# Modbus_RTU.net
KiCad netlist of a schematic drawn in Altium Designer
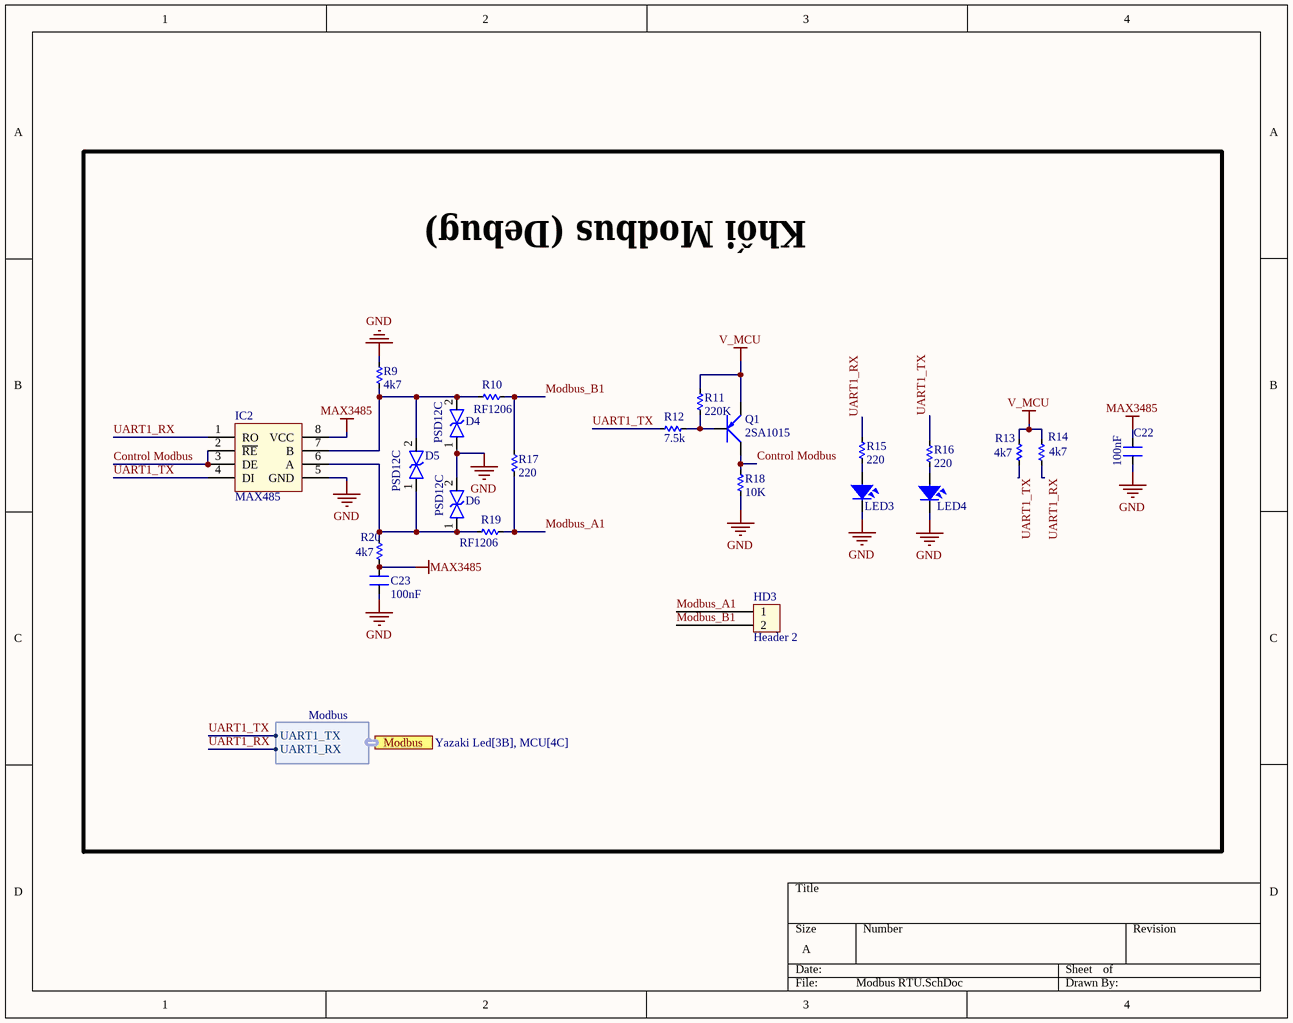
[diagram p0: Modbus RTU.SchDoc]

(export (version "E")
  (design (tool "Eeschema 10.0.6"))
  (components
    (comp (ref "C22") (value "100nF") (footprint "CN-SMD-0603") (libsource (lib "thu vien 3d") (part "CN")))
    (comp (ref "C23") (value "100nF") (footprint "CN-SMD-0603") (libsource (lib "thu vien 3d") (part "CN")))
    (comp (ref "D4")
      (value "PSD12C")
      (footprint "PSD12C")
      (description "diode tvs")
      (libsource (lib "Nichietsuvn") (part "PSD12C"))
    )
    (comp (ref "D5")
      (value "PSD12C")
      (footprint "PSD12C")
      (description "diode tvs")
      (libsource (lib "Nichietsuvn") (part "PSD12C"))
    )
    (comp (ref "D6")
      (value "PSD12C")
      (footprint "PSD12C")
      (description "diode tvs")
      (libsource (lib "Nichietsuvn") (part "PSD12C"))
    )
    (comp (ref "HD3") (value "Header 2") (footprint "Header_2") (libsource (lib "lpson") (part "Header2")))
    (comp (ref "IC2")
      (value "MAX485")
      (footprint "SO8")
      (description "RS232 - RS485 (Same sn75176)")
      (libsource (lib "thu vien 3d") (part "MAX485"))
    )
    (comp (ref "LED3")
      (value "LED")
      (footprint "LED-0805-Blue")
      (libsource (lib "thu vien 3d") (part "LED SMD"))
    )
    (comp (ref "LED4")
      (value "LED")
      (footprint "LED-0805-Blue")
      (libsource (lib "thu vien 3d") (part "LED SMD"))
    )
    (comp (ref "Q1")
      (value "2SA1015")
      (footprint "SOT23-321")
      (description "PNP 600mW, ECB")
      (libsource (lib "thu vien 3d") (part "2SA1015"))
    )
    (comp (ref "R9")
      (value "4k7")
      (footprint "RES-SMD-0603")
      (description "Resistor")
      (fields
        (field (name "MANUFACTURER") "Generic Components")
        (field (name "PUBLISHER") "Altium Hobart Technology Centre")
      )
      (libsource (lib "thu vien 3d") (part "Res-SMD"))
    )
    (comp (ref "R10")
      (value "RF1206")
      (footprint "RES-SMD-1206")
      (description "Resistor")
      (fields
        (field (name "MANUFACTURER") "Generic Components")
        (field (name "PUBLISHER") "Altium Hobart Technology Centre")
      )
      (libsource (lib "thu vien 3d") (part "Res-SMD"))
    )
    (comp (ref "R11")
      (value "220K")
      (footprint "RES-SMD-0603")
      (description "Resistor")
      (fields
        (field (name "MANUFACTURER") "Generic Components")
        (field (name "PUBLISHER") "Altium Hobart Technology Centre")
      )
      (libsource (lib "thu vien 3d") (part "Res-SMD"))
    )
    (comp (ref "R12")
      (value "7.5k")
      (footprint "RES-SMD-0603")
      (description "Resistor")
      (fields
        (field (name "MANUFACTURER") "Generic Components")
        (field (name "PUBLISHER") "Altium Hobart Technology Centre")
      )
      (libsource (lib "thu vien 3d") (part "Res-SMD"))
    )
    (comp (ref "R13")
      (value "4k7")
      (footprint "RES-SMD-0603")
      (description "Resistor")
      (fields
        (field (name "MANUFACTURER") "Generic Components")
        (field (name "PUBLISHER") "Altium Hobart Technology Centre")
      )
      (libsource (lib "thu vien 3d") (part "Res-SMD"))
    )
    (comp (ref "R14")
      (value "4k7")
      (footprint "RES-SMD-0603")
      (description "Resistor")
      (fields
        (field (name "MANUFACTURER") "Generic Components")
        (field (name "PUBLISHER") "Altium Hobart Technology Centre")
      )
      (libsource (lib "thu vien 3d") (part "Res-SMD"))
    )
    (comp (ref "R15")
      (value "220")
      (footprint "RES-SMD-0603")
      (description "Resistor")
      (fields
        (field (name "MANUFACTURER") "Generic Components")
        (field (name "PUBLISHER") "Altium Hobart Technology Centre")
      )
      (libsource (lib "thu vien 3d") (part "Res-SMD"))
    )
    (comp (ref "R16")
      (value "220")
      (footprint "RES-SMD-0603")
      (description "Resistor")
      (fields
        (field (name "MANUFACTURER") "Generic Components")
        (field (name "PUBLISHER") "Altium Hobart Technology Centre")
      )
      (libsource (lib "thu vien 3d") (part "Res-SMD"))
    )
    (comp (ref "R17")
      (value "220")
      (footprint "RES-SMD-0603")
      (description "Resistor")
      (fields
        (field (name "MANUFACTURER") "Generic Components")
        (field (name "PUBLISHER") "Altium Hobart Technology Centre")
      )
      (libsource (lib "thu vien 3d") (part "Res-SMD"))
    )
    (comp (ref "R18")
      (value "10K")
      (footprint "RES-SMD-0603")
      (description "Resistor")
      (fields
        (field (name "MANUFACTURER") "Generic Components")
        (field (name "PUBLISHER") "Altium Hobart Technology Centre")
      )
      (libsource (lib "thu vien 3d") (part "Res-SMD"))
    )
    (comp (ref "R19")
      (value "RF1206")
      (footprint "RES-SMD-1206")
      (description "Resistor")
      (fields
        (field (name "MANUFACTURER") "Generic Components")
        (field (name "PUBLISHER") "Altium Hobart Technology Centre")
      )
      (libsource (lib "thu vien 3d") (part "Res-SMD"))
    )
    (comp (ref "R20")
      (value "4k7")
      (footprint "RES-SMD-0603")
      (description "Resistor")
      (fields
        (field (name "MANUFACTURER") "Generic Components")
        (field (name "PUBLISHER") "Altium Hobart Technology Centre")
      )
      (libsource (lib "thu vien 3d") (part "Res-SMD"))
    )
  )
  (nets
    (net (code "2") (name "/Control Modbus") (class "Default")
      (node (ref "IC2") (pin "2") (pinfunction "~{RE}_2") (pintype "passive"))
      (node (ref "IC2") (pin "3") (pinfunction "DE_3") (pintype "passive"))
      (node (ref "Q1") (pin "2") (pinfunction "C_2") (pintype "passive"))
      (node (ref "R18") (pin "2") (pinfunction "2_2") (pintype "passive"))
    )
    (net (code "3") (name "/Modbus_A1") (class "Default")
      (node (ref "HD3") (pin "1") (pinfunction "1_1") (pintype "passive"))
      (node (ref "R17") (pin "2") (pinfunction "2_2") (pintype "passive"))
      (node (ref "R19") (pin "1") (pinfunction "1_1") (pintype "passive"))
    )
    (net (code "4") (name "/Modbus_B1") (class "Default")
      (node (ref "HD3") (pin "2") (pinfunction "2_2") (pintype "passive"))
      (node (ref "R10") (pin "1") (pinfunction "1_1") (pintype "passive"))
      (node (ref "R17") (pin "1") (pinfunction "1_1") (pintype "passive"))
    )
    (net (code "5") (name "/UART1_RX") (class "Default")
      (node (ref "IC2") (pin "1") (pinfunction "RO_1") (pintype "passive"))
      (node (ref "R14") (pin "2") (pinfunction "2_2") (pintype "passive"))
      (node (ref "R15") (pin "1") (pinfunction "1_1") (pintype "passive"))
    )
    (net (code "6") (name "/UART1_TX") (class "Default")
      (node (ref "IC2") (pin "4") (pinfunction "DI_4") (pintype "passive"))
      (node (ref "R12") (pin "1") (pinfunction "1_1") (pintype "passive"))
      (node (ref "R13") (pin "2") (pinfunction "2_2") (pintype "passive"))
      (node (ref "R16") (pin "1") (pinfunction "1_1") (pintype "passive"))
    )
    (net (code "8") (name "GND") (class "Default")
      (node (ref "C22") (pin "1") (pinfunction "1_1") (pintype "passive"))
      (node (ref "C23") (pin "2") (pinfunction "2_2") (pintype "passive"))
      (node (ref "D4") (pin "1") (pinfunction "1_1") (pintype "passive"))
      (node (ref "D6") (pin "2") (pinfunction "2_2") (pintype "passive"))
      (node (ref "IC2") (pin "5") (pinfunction "GND_5") (pintype "passive"))
      (node (ref "LED3") (pin "2") (pinfunction "2_2") (pintype "passive"))
      (node (ref "LED4") (pin "2") (pinfunction "2_2") (pintype "passive"))
      (node (ref "R18") (pin "1") (pinfunction "1_1") (pintype "passive"))
      (node (ref "R9") (pin "1") (pinfunction "1_1") (pintype "passive"))
    )
    (net (code "9") (name "MAX3485") (class "Default")
      (node (ref "C22") (pin "2") (pinfunction "2_2") (pintype "passive"))
      (node (ref "C23") (pin "1") (pinfunction "1_1") (pintype "passive"))
      (node (ref "IC2") (pin "8") (pinfunction "VCC_8") (pintype "passive"))
      (node (ref "R20") (pin "1") (pinfunction "1_1") (pintype "passive"))
    )
    (net (code "10") (name "Net-(IC2-A)") (class "Default")
      (node (ref "D5") (pin "1") (pinfunction "1_1") (pintype "passive"))
      (node (ref "D6") (pin "1") (pinfunction "1_1") (pintype "passive"))
      (node (ref "IC2") (pin "6") (pinfunction "A_6") (pintype "passive"))
      (node (ref "R19") (pin "2") (pinfunction "2_2") (pintype "passive"))
      (node (ref "R20") (pin "2") (pinfunction "2_2") (pintype "passive"))
    )
    (net (code "11") (name "Net-(IC2-B)") (class "Default")
      (node (ref "D4") (pin "2") (pinfunction "2_2") (pintype "passive"))
      (node (ref "D5") (pin "2") (pinfunction "2_2") (pintype "passive"))
      (node (ref "IC2") (pin "7") (pinfunction "B_7") (pintype "passive"))
      (node (ref "R10") (pin "2") (pinfunction "2_2") (pintype "passive"))
      (node (ref "R9") (pin "2") (pinfunction "2_2") (pintype "passive"))
    )
    (net (code "12") (name "Net-(LED3-Pad1)") (class "Default")
      (node (ref "LED3") (pin "1") (pinfunction "1_1") (pintype "passive"))
      (node (ref "R15") (pin "2") (pinfunction "2_2") (pintype "passive"))
    )
    (net (code "13") (name "Net-(LED4-Pad1)") (class "Default")
      (node (ref "LED4") (pin "1") (pinfunction "1_1") (pintype "passive"))
      (node (ref "R16") (pin "2") (pinfunction "2_2") (pintype "passive"))
    )
    (net (code "14") (name "Net-(Q1-B)") (class "Default")
      (node (ref "Q1") (pin "3") (pinfunction "B_3") (pintype "passive"))
      (node (ref "R11") (pin "1") (pinfunction "1_1") (pintype "passive"))
      (node (ref "R12") (pin "2") (pinfunction "2_2") (pintype "passive"))
    )
    (net (code "15") (name "V_MCU") (class "Default")
      (node (ref "Q1") (pin "1") (pinfunction "E_1") (pintype "passive"))
      (node (ref "R11") (pin "2") (pinfunction "2_2") (pintype "passive"))
      (node (ref "R13") (pin "1") (pinfunction "1_1") (pintype "passive"))
      (node (ref "R14") (pin "1") (pinfunction "1_1") (pintype "passive"))
    )
  )
)
